# RTC.net
KiCad netlist of a schematic drawn in Altium Designer
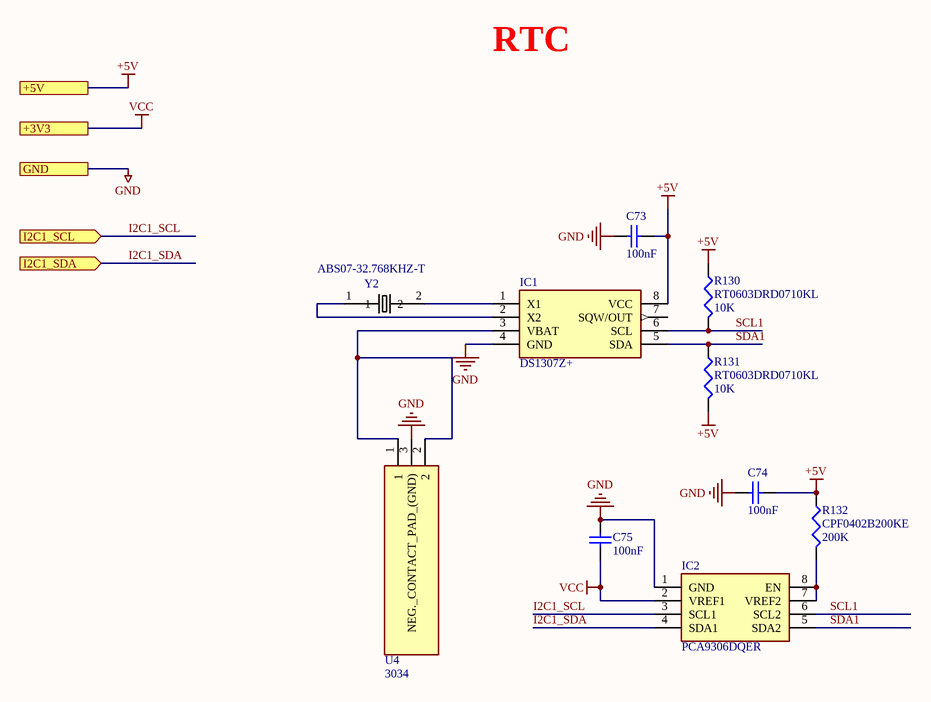
[diagram p0: RTC.SchDoc]

(export (version "E")
  (design (tool "Eeschema 10.0.6"))
  (components
    (comp (ref "C73")
      (value "100nF")
      (footprint "CAPC1005X55X30LL05T10")
      (libsource (lib "Altium Content Vault") (part "CAP"))
    )
    (comp (ref "C74")
      (value "100nF")
      (footprint "CAPC1005X55X30LL05T10")
      (libsource (lib "Altium Content Vault") (part "CAP"))
    )
    (comp (ref "C75")
      (value "100nF")
      (footprint "CAPC1005X55X30LL05T10")
      (libsource (lib "Altium Content Vault") (part "CAP"))
    )
    (comp (ref "IC1")
      (value "DS1307Z+")
      (footprint "S8-2_M")
      (description "Integrated Circuit")
      (fields (field (name "MOUSER PART NUMBER") "700-DS1307Z") (field (name "RS PART NUMBER") "1698316"))
      (libsource (lib "*") (part "DS1307Z+"))
    )
    (comp (ref "IC2")
      (value "PCA9306DQER")
      (footprint "FP-DQE0008A-MFG")
      (description "Integrated Circuit")
      (fields (field (name "MOUSER PART NUMBER") "595-PCA9306DQER"))
      (libsource (lib "*") (part "PCA9306DQER"))
    )
    (comp (ref "R130")
      (value "RT0603DRD0710KL")
      (footprint "J1-0603")
      (description "Resistor")
      (fields (field (name "ALTIUM_VALUE") "10K") (field (name "PUBLISHER") "Altium Limited"))
      (libsource (lib "Miscellaneous Devices") (part "Res3"))
    )
    (comp (ref "R131")
      (value "RT0603DRD0710KL")
      (footprint "J1-0603")
      (description "Resistor")
      (fields (field (name "ALTIUM_VALUE") "10K") (field (name "PUBLISHER") "Altium Limited"))
      (libsource (lib "Miscellaneous Devices") (part "Res3"))
    )
    (comp (ref "R132")
      (value "CPF0402B200KE")
      (footprint "0402")
      (description "Resistor")
      (fields (field (name "ALTIUM_VALUE") "200K") (field (name "PUBLISHER") "Altium Limited"))
      (libsource (lib "Miscellaneous Devices") (part "Res3"))
    )
    (comp (ref "U4")
      (value "3034")
      (footprint "FP-3034-MFG")
      (description "CR2032 COINCELL 3V BATTERY Holder")
      (fields (field (name "MOUSER PART NUMBER") "534-3034"))
      (libsource (lib "*") (part "3034"))
    )
    (comp (ref "Y2")
      (value "ABS07-32.768KHZ-T")
      (footprint "FP-ABS07-MFG")
      (description "ABS07 Series 32.768 kHz Â±20 ppm 12.5 pF -40 to +85 Â°C SMT Low Profile Crystal")
      (fields (field (name "MF") "Abracon"))
      (libsource (lib "Crystal 2SMD ABS-32.768KHZ-T") (part "ABS07-32.768KHZ-T"))
    )
  )
  (nets
    (net (code "1") (name "+5V") (class "Default")
      (node (ref "C73") (pin "1") (pinfunction "1_1") (pintype "passive"))
      (node (ref "C74") (pin "1") (pinfunction "1_1") (pintype "passive"))
      (node (ref "IC1") (pin "8") (pinfunction "VCC_8") (pintype "power_in"))
      (node (ref "R130") (pin "1") (pinfunction "1_1") (pintype "passive"))
      (node (ref "R131") (pin "2") (pinfunction "2_2") (pintype "passive"))
      (node (ref "R132") (pin "1") (pinfunction "1_1") (pintype "passive"))
    )
    (net (code "2") (name "/I2C1_SCL") (class "Default")
      (node (ref "IC2") (pin "3") (pinfunction "SCL1_3") (pintype "passive"))
    )
    (net (code "3") (name "/I2C1_SDA") (class "Default")
      (node (ref "IC2") (pin "4") (pinfunction "SDA1_4") (pintype "passive"))
    )
    (net (code "4") (name "/SCL1") (class "Default")
      (node (ref "IC1") (pin "6") (pinfunction "SCL_6") (pintype "passive"))
      (node (ref "IC2") (pin "6") (pinfunction "SCL2_6") (pintype "passive"))
      (node (ref "R130") (pin "2") (pinfunction "2_2") (pintype "passive"))
    )
    (net (code "5") (name "/SDA1") (class "Default")
      (node (ref "IC1") (pin "5") (pinfunction "SDA_5") (pintype "passive"))
      (node (ref "IC2") (pin "5") (pinfunction "SDA2_5") (pintype "passive"))
      (node (ref "R131") (pin "1") (pinfunction "1_1") (pintype "passive"))
    )
    (net (code "6") (name "GND") (class "Default")
      (node (ref "C73") (pin "2") (pinfunction "2_2") (pintype "passive"))
      (node (ref "C74") (pin "2") (pinfunction "2_2") (pintype "passive"))
      (node (ref "C75") (pin "2") (pinfunction "2_2") (pintype "passive"))
      (node (ref "IC1") (pin "4") (pinfunction "GND_4") (pintype "power_in"))
      (node (ref "IC2") (pin "1") (pinfunction "GND_1") (pintype "passive"))
      (node (ref "U4") (pin "3") (pinfunction "NEG._CONTACT_PAD_(GND)_3") (pintype "passive"))
    )
    (net (code "7") (name "Net-(IC1-VBAT)") (class "Default")
      (node (ref "IC1") (pin "3") (pinfunction "VBAT_3") (pintype "passive"))
      (node (ref "U4") (pin "1") (pinfunction "1_1") (pintype "passive"))
      (node (ref "U4") (pin "2") (pinfunction "2_2") (pintype "passive"))
    )
    (net (code "8") (name "Net-(IC1-X1)") (class "Default")
      (node (ref "IC1") (pin "1") (pinfunction "X1_1") (pintype "passive"))
      (node (ref "Y2") (pin "2") (pinfunction "2_2") (pintype "passive"))
    )
    (net (code "9") (name "Net-(IC1-X2)") (class "Default")
      (node (ref "IC1") (pin "2") (pinfunction "X2_2") (pintype "passive"))
      (node (ref "Y2") (pin "1") (pinfunction "1_1") (pintype "passive"))
    )
    (net (code "10") (name "Net-(IC2-EN)") (class "Default")
      (node (ref "IC2") (pin "7") (pinfunction "VREF2_7") (pintype "passive"))
      (node (ref "IC2") (pin "8") (pinfunction "EN_8") (pintype "passive"))
      (node (ref "R132") (pin "2") (pinfunction "2_2") (pintype "passive"))
    )
    (net (code "11") (name "VCC") (class "Default")
      (node (ref "C75") (pin "1") (pinfunction "1_1") (pintype "passive"))
      (node (ref "IC2") (pin "2") (pinfunction "VREF1_2") (pintype "passive"))
    )
    (net (code "12") (name "unconnected-(IC1-SQW{slash}OUT-Pad7)") (class "Default")
      (node (ref "IC1") (pin "7") (pinfunction "SQW/OUT_7") (pintype "output"))
    )
  )
)
